# HCPL-3120_DIP_Gate_Driver_Circuit.net
KiCad netlist of a schematic drawn in Altium Designer
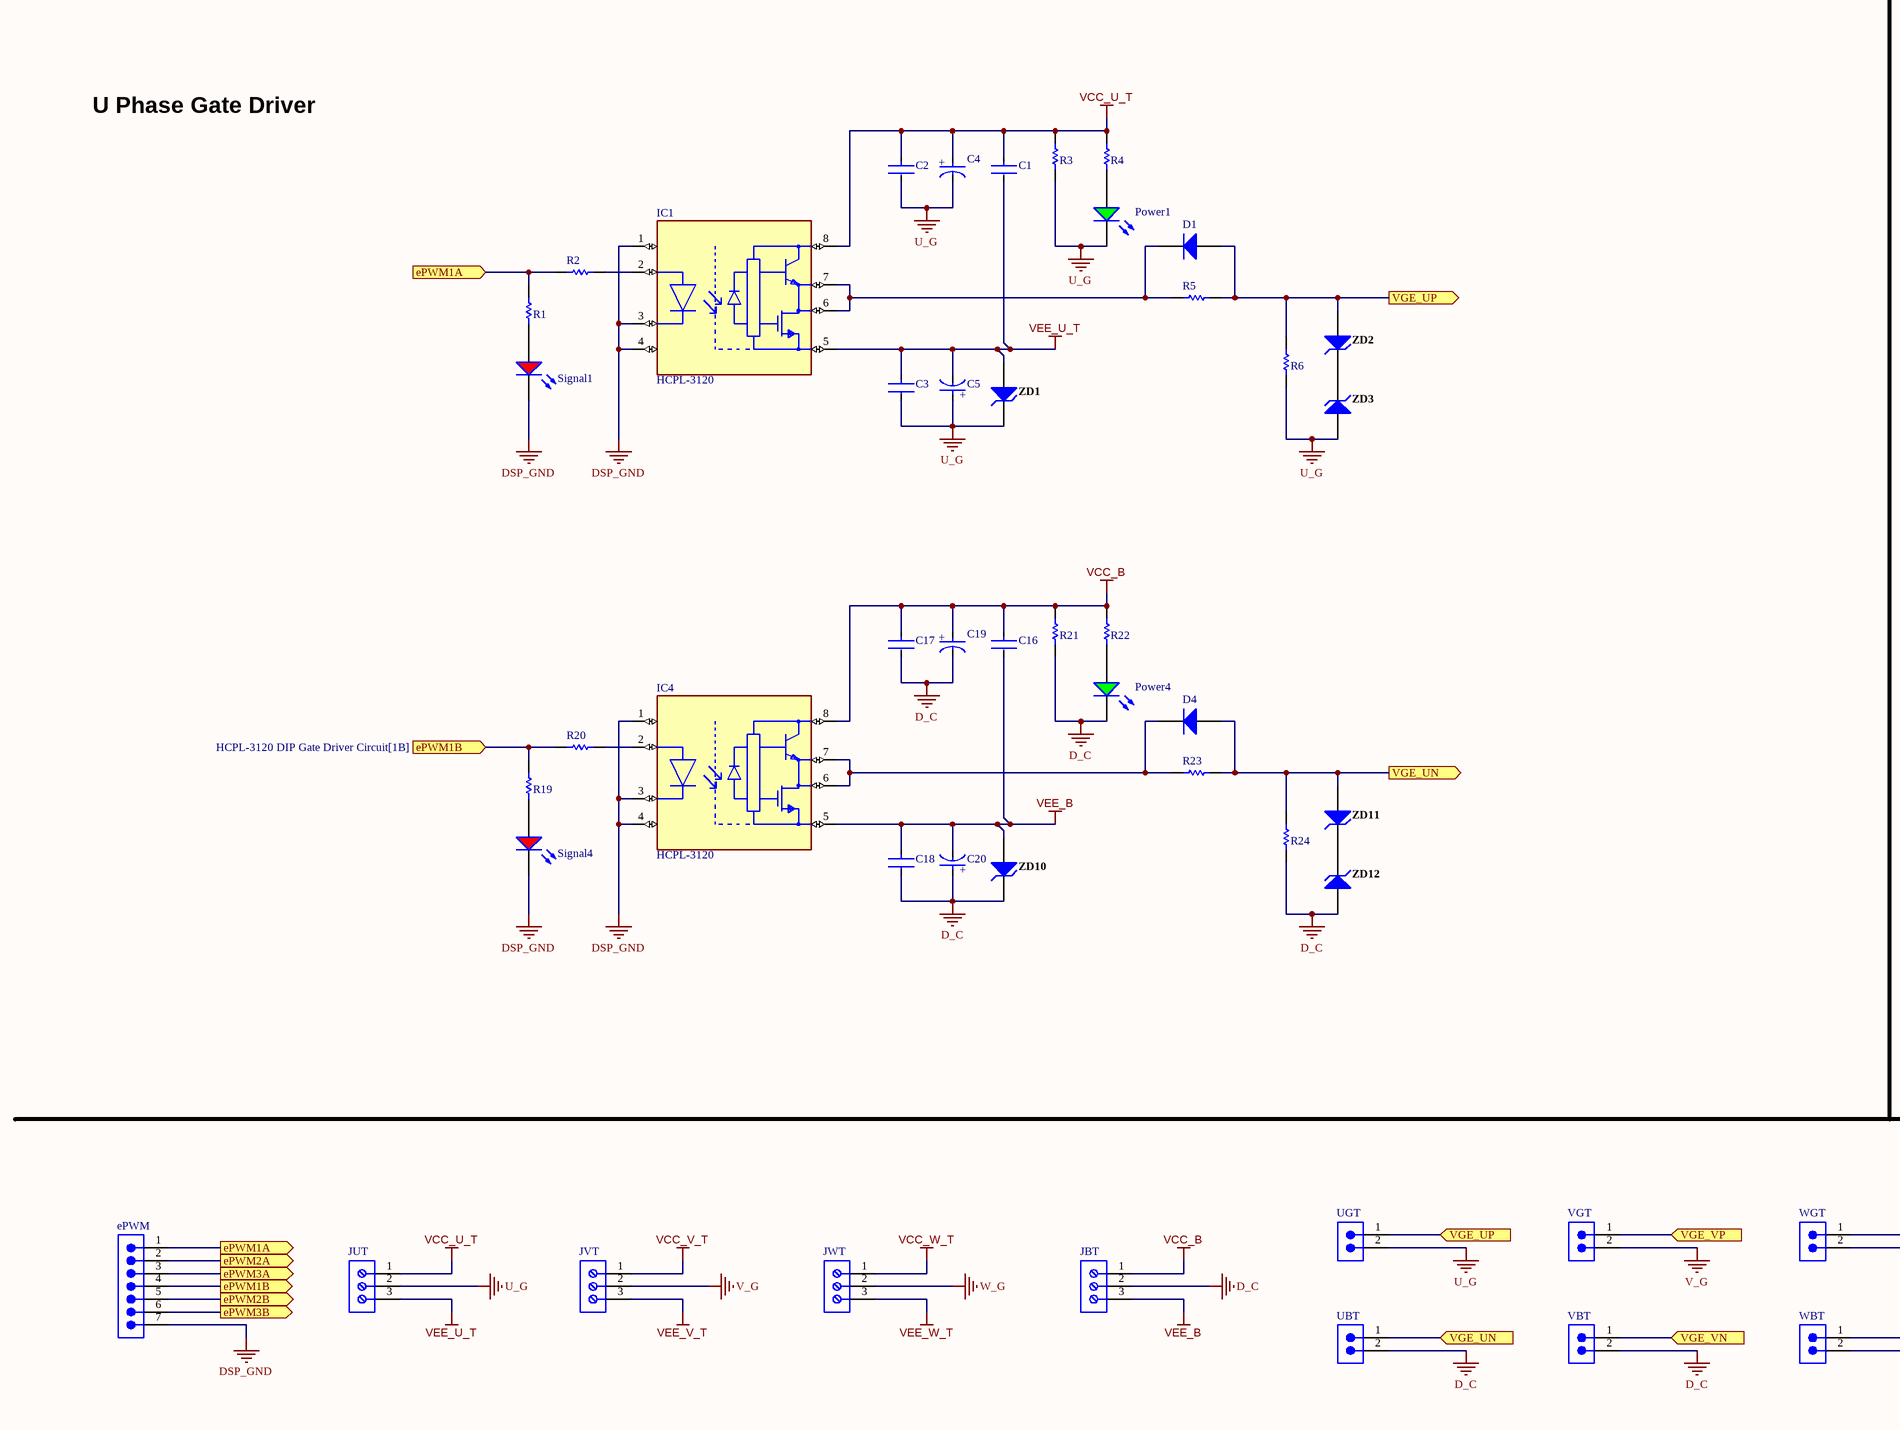
[diagram p0: HCPL-3120 DIP Gate Driver Circuit.SchDoc, left]
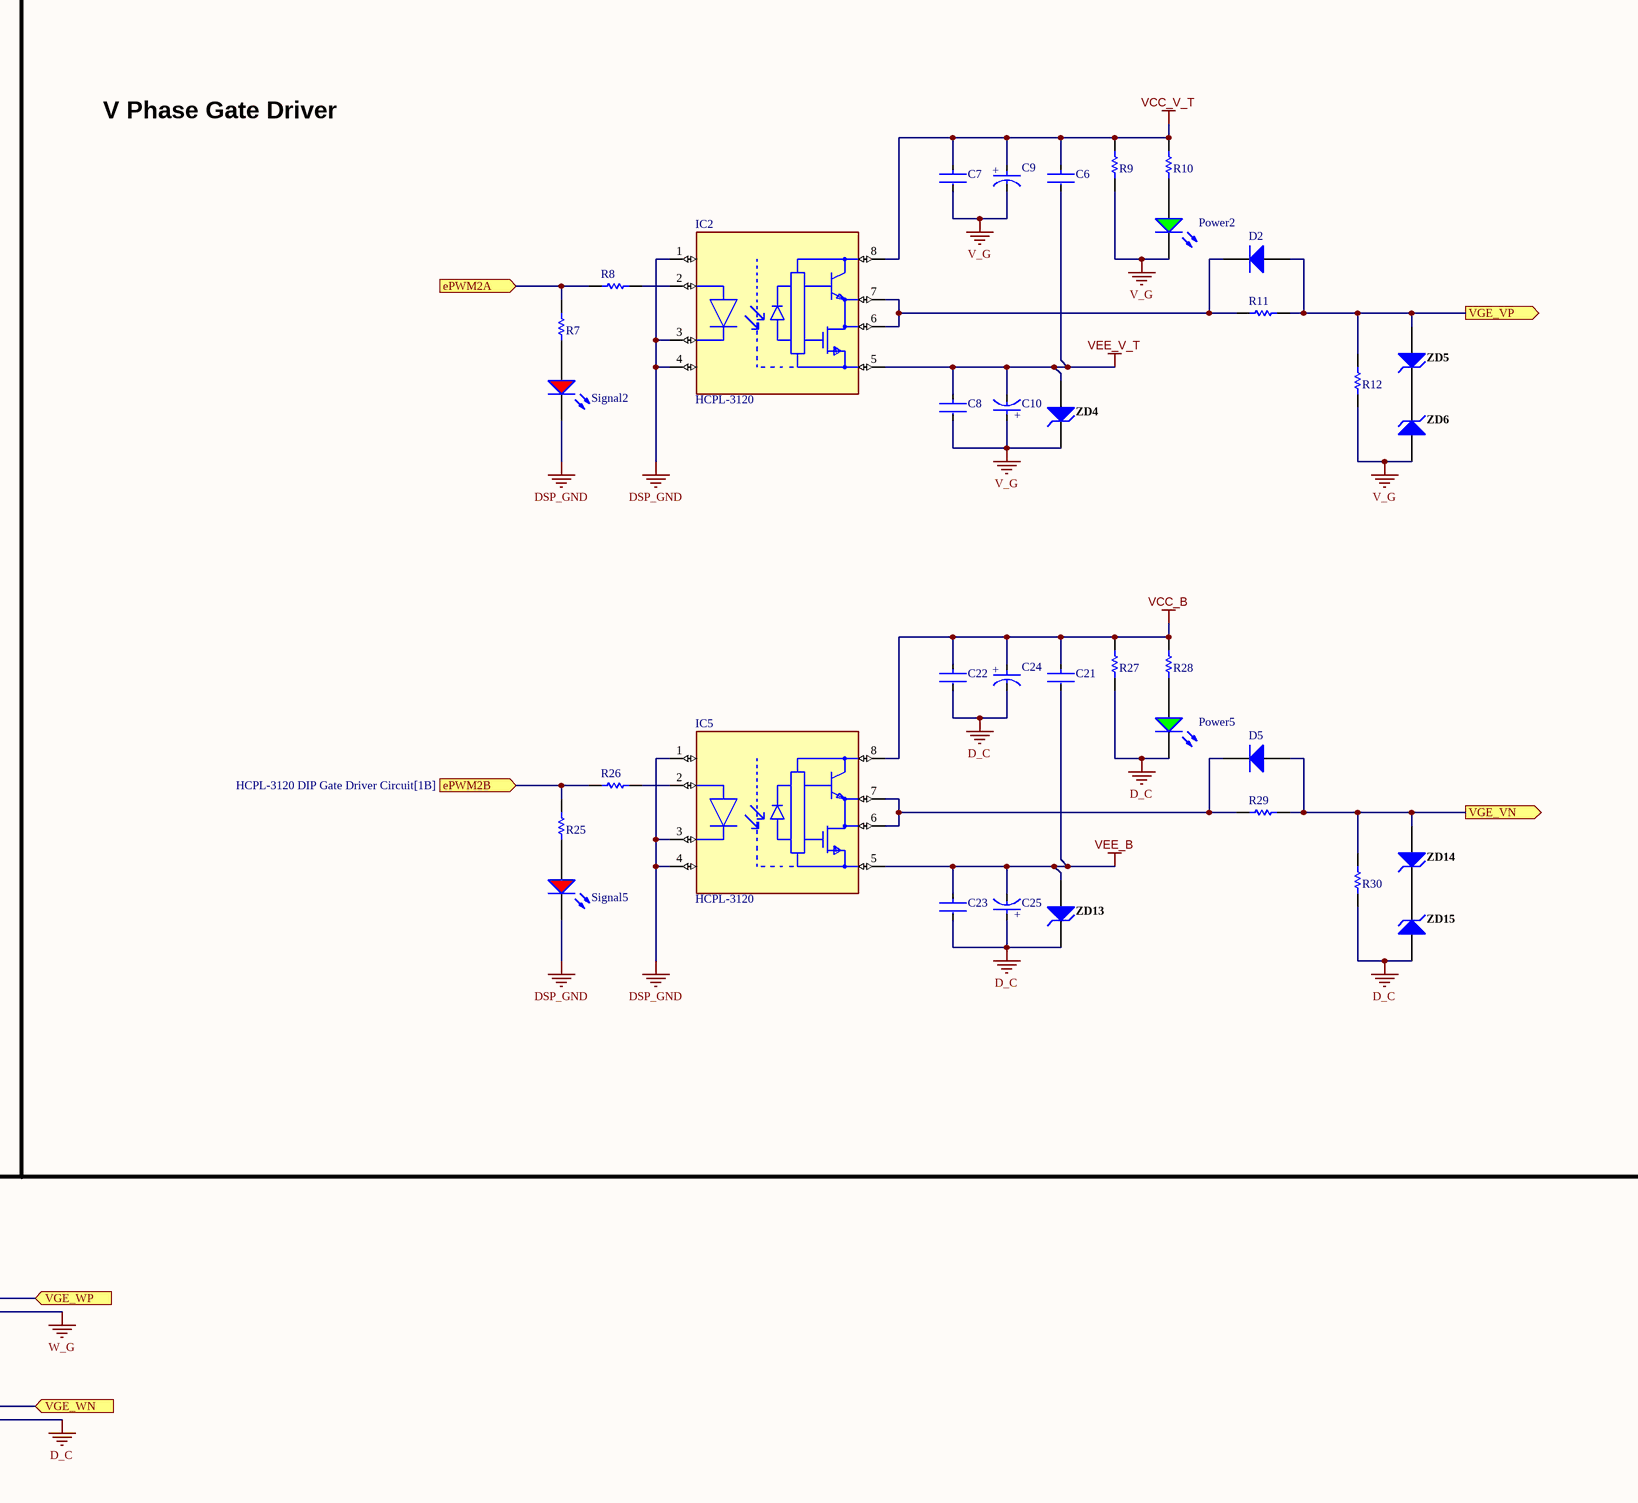
[diagram p1: HCPL-3120 DIP Gate Driver Circuit.SchDoc, middle]
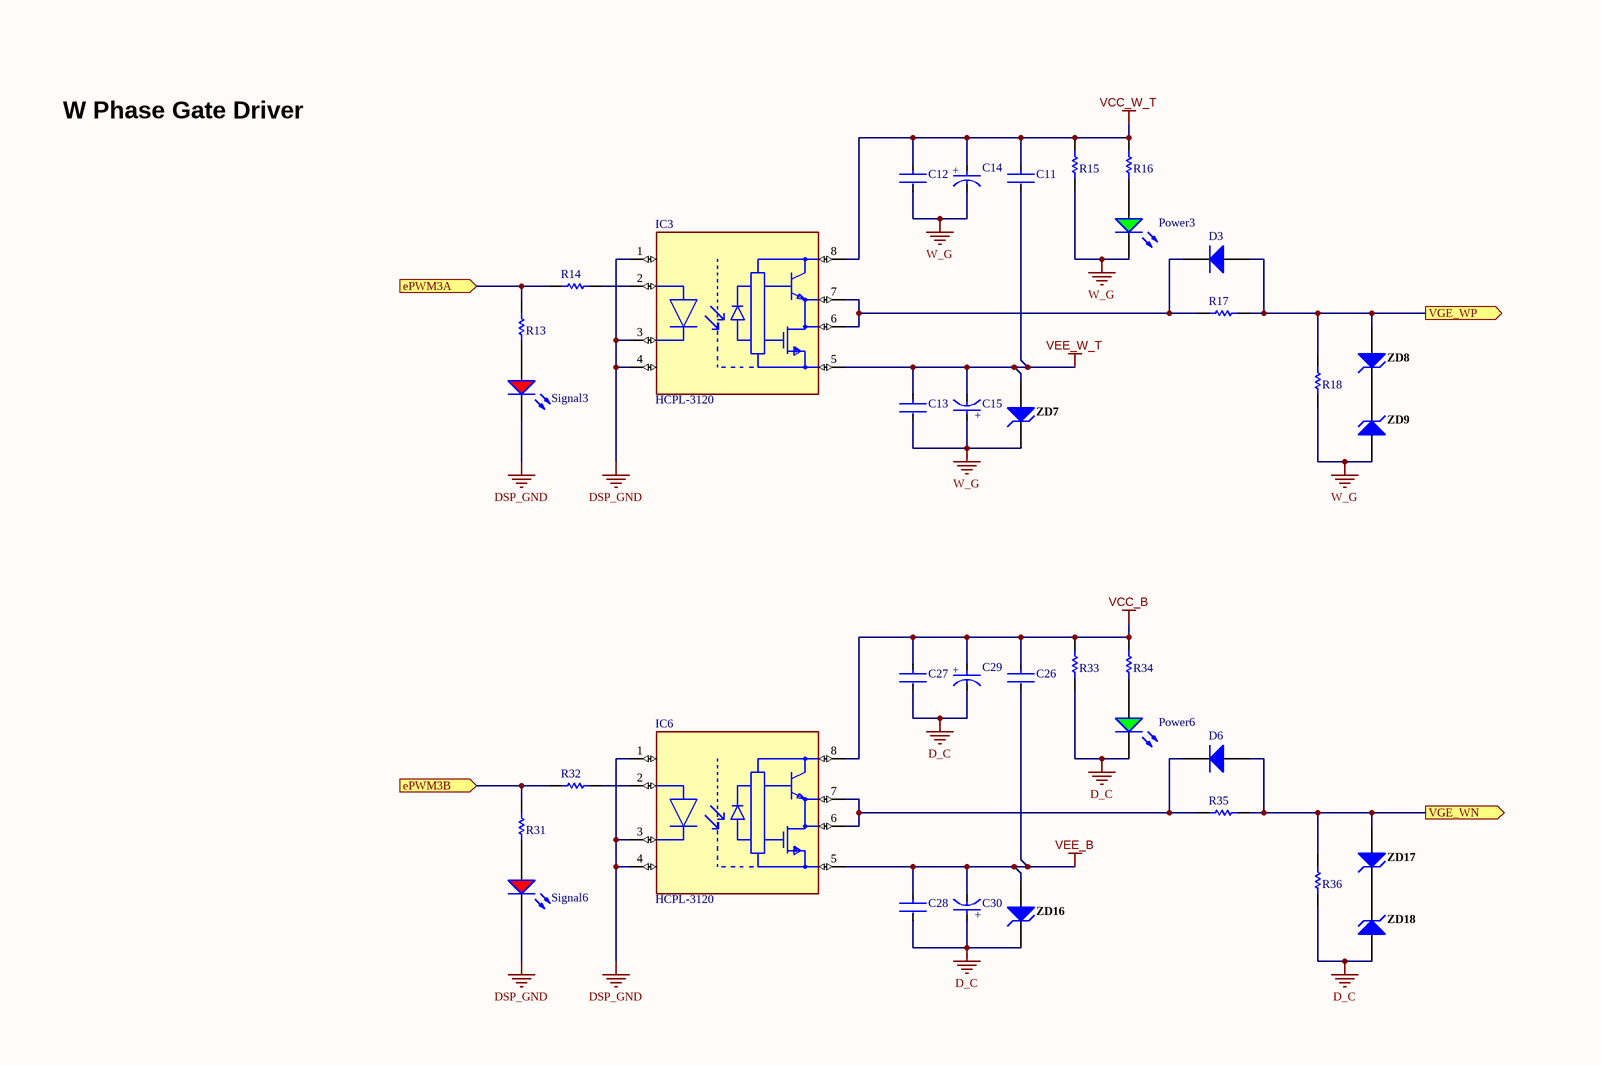
[diagram p2: HCPL-3120 DIP Gate Driver Circuit.SchDoc, right]

(export (version "E")
  (design (tool "Eeschema 10.0.6"))
  (components
    (comp (ref "C1")
      (value "SR205C104KAR")
      (footprint "FP-SR20-MFG")
      (description "CAP CER 0.1UF 50V X7R RADIAL")
      (fields (field (name "VOLTAGE") "50V") (field (name "TOLERANCE") "10%"))
      (libsource (lib "Altium Content Vault") (part "11868f565c42a9108669ba33697ecf6"))
    )
    (comp (ref "C2")
      (value "SR205C104KAR")
      (footprint "FP-SR20-MFG")
      (description "CAP CER 0.1UF 50V X7R RADIAL")
      (fields (field (name "VOLTAGE") "50V") (field (name "TOLERANCE") "10%"))
      (libsource (lib "Altium Content Vault") (part "11868f565c42a9108669ba33697ecf6"))
    )
    (comp (ref "C3")
      (value "SR205C104KAR")
      (footprint "FP-SR20-MFG")
      (description "CAP CER 0.1UF 50V X7R RADIAL")
      (fields (field (name "VOLTAGE") "50V") (field (name "TOLERANCE") "10%"))
      (libsource (lib "Altium Content Vault") (part "11868f565c42a9108669ba33697ecf6"))
    )
    (comp (ref "C4")
      (value "EEUTA1H101")
      (footprint "FP-RAD-TH-D_10_0_5-L_12_5-MFG")
      (description "Aluminum Electrolytic Capacitors (Radial Lead Type) AEC-Q200 Qualified 100uF ±20% 50V")
      (fields (field (name "TOLERANCE") "20%"))
      (libsource (lib "Altium Content Vault") (part "203bc49f2ac43e59fd269a8c329ed05"))
    )
    (comp (ref "C5")
      (value "EEUTA1H101")
      (footprint "FP-RAD-TH-D_10_0_5-L_12_5-MFG")
      (description "Aluminum Electrolytic Capacitors (Radial Lead Type) AEC-Q200 Qualified 100uF ±20% 50V")
      (fields (field (name "TOLERANCE") "20%"))
      (libsource (lib "Altium Content Vault") (part "203bc49f2ac43e59fd269a8c329ed05"))
    )
    (comp (ref "C6")
      (value "SR205C104KAR")
      (footprint "FP-SR20-MFG")
      (description "CAP CER 0.1UF 50V X7R RADIAL")
      (fields (field (name "VOLTAGE") "50V") (field (name "TOLERANCE") "10%"))
      (libsource (lib "Altium Content Vault") (part "11868f565c42a9108669ba33697ecf6"))
    )
    (comp (ref "C7")
      (value "SR205C104KAR")
      (footprint "FP-SR20-MFG")
      (description "CAP CER 0.1UF 50V X7R RADIAL")
      (fields (field (name "VOLTAGE") "50V") (field (name "TOLERANCE") "10%"))
      (libsource (lib "Altium Content Vault") (part "11868f565c42a9108669ba33697ecf6"))
    )
    (comp (ref "C8")
      (value "SR205C104KAR")
      (footprint "FP-SR20-MFG")
      (description "CAP CER 0.1UF 50V X7R RADIAL")
      (fields (field (name "VOLTAGE") "50V") (field (name "TOLERANCE") "10%"))
      (libsource (lib "Altium Content Vault") (part "11868f565c42a9108669ba33697ecf6"))
    )
    (comp (ref "C9")
      (value "EEUTA1H101")
      (footprint "FP-RAD-TH-D_10_0_5-L_12_5-MFG")
      (description "Aluminum Electrolytic Capacitors (Radial Lead Type) AEC-Q200 Qualified 100uF ±20% 50V")
      (fields (field (name "TOLERANCE") "20%"))
      (libsource (lib "Altium Content Vault") (part "203bc49f2ac43e59fd269a8c329ed05"))
    )
    (comp (ref "C10")
      (value "EEUTA1H101")
      (footprint "FP-RAD-TH-D_10_0_5-L_12_5-MFG")
      (description "Aluminum Electrolytic Capacitors (Radial Lead Type) AEC-Q200 Qualified 100uF ±20% 50V")
      (fields (field (name "TOLERANCE") "20%"))
      (libsource (lib "Altium Content Vault") (part "203bc49f2ac43e59fd269a8c329ed05"))
    )
    (comp (ref "C11")
      (value "SR205C104KAR")
      (footprint "FP-SR20-MFG")
      (description "CAP CER 0.1UF 50V X7R RADIAL")
      (fields (field (name "VOLTAGE") "50V") (field (name "TOLERANCE") "10%"))
      (libsource (lib "Altium Content Vault") (part "11868f565c42a9108669ba33697ecf6"))
    )
    (comp (ref "C12")
      (value "SR205C104KAR")
      (footprint "FP-SR20-MFG")
      (description "CAP CER 0.1UF 50V X7R RADIAL")
      (fields (field (name "VOLTAGE") "50V") (field (name "TOLERANCE") "10%"))
      (libsource (lib "Altium Content Vault") (part "11868f565c42a9108669ba33697ecf6"))
    )
    (comp (ref "C13")
      (value "SR205C104KAR")
      (footprint "FP-SR20-MFG")
      (description "CAP CER 0.1UF 50V X7R RADIAL")
      (fields (field (name "VOLTAGE") "50V") (field (name "TOLERANCE") "10%"))
      (libsource (lib "Altium Content Vault") (part "11868f565c42a9108669ba33697ecf6"))
    )
    (comp (ref "C14")
      (value "EEUTA1H101")
      (footprint "FP-RAD-TH-D_10_0_5-L_12_5-MFG")
      (description "Aluminum Electrolytic Capacitors (Radial Lead Type) AEC-Q200 Qualified 100uF ±20% 50V")
      (fields (field (name "TOLERANCE") "20%"))
      (libsource (lib "Altium Content Vault") (part "203bc49f2ac43e59fd269a8c329ed05"))
    )
    (comp (ref "C15")
      (value "EEUTA1H101")
      (footprint "FP-RAD-TH-D_10_0_5-L_12_5-MFG")
      (description "Aluminum Electrolytic Capacitors (Radial Lead Type) AEC-Q200 Qualified 100uF ±20% 50V")
      (fields (field (name "TOLERANCE") "20%"))
      (libsource (lib "Altium Content Vault") (part "203bc49f2ac43e59fd269a8c329ed05"))
    )
    (comp (ref "C16")
      (value "SR205C104KAR")
      (footprint "FP-SR20-MFG")
      (description "CAP CER 0.1UF 50V X7R RADIAL")
      (fields (field (name "VOLTAGE") "50V") (field (name "TOLERANCE") "10%"))
      (libsource (lib "Altium Content Vault") (part "11868f565c42a9108669ba33697ecf6"))
    )
    (comp (ref "C17")
      (value "SR205C104KAR")
      (footprint "FP-SR20-MFG")
      (description "CAP CER 0.1UF 50V X7R RADIAL")
      (fields (field (name "VOLTAGE") "50V") (field (name "TOLERANCE") "10%"))
      (libsource (lib "Altium Content Vault") (part "11868f565c42a9108669ba33697ecf6"))
    )
    (comp (ref "C18")
      (value "SR205C104KAR")
      (footprint "FP-SR20-MFG")
      (description "CAP CER 0.1UF 50V X7R RADIAL")
      (fields (field (name "VOLTAGE") "50V") (field (name "TOLERANCE") "10%"))
      (libsource (lib "Altium Content Vault") (part "11868f565c42a9108669ba33697ecf6"))
    )
    (comp (ref "C19")
      (value "EEUTA1H101")
      (footprint "FP-RAD-TH-D_10_0_5-L_12_5-MFG")
      (description "Aluminum Electrolytic Capacitors (Radial Lead Type) AEC-Q200 Qualified 100uF ±20% 50V")
      (fields (field (name "TOLERANCE") "20%"))
      (libsource (lib "Altium Content Vault") (part "203bc49f2ac43e59fd269a8c329ed05"))
    )
    (comp (ref "C20")
      (value "EEUTA1H101")
      (footprint "FP-RAD-TH-D_10_0_5-L_12_5-MFG")
      (description "Aluminum Electrolytic Capacitors (Radial Lead Type) AEC-Q200 Qualified 100uF ±20% 50V")
      (fields (field (name "TOLERANCE") "20%"))
      (libsource (lib "Altium Content Vault") (part "203bc49f2ac43e59fd269a8c329ed05"))
    )
    (comp (ref "C21")
      (value "SR205C104KAR")
      (footprint "FP-SR20-MFG")
      (description "CAP CER 0.1UF 50V X7R RADIAL")
      (fields (field (name "VOLTAGE") "50V") (field (name "TOLERANCE") "10%"))
      (libsource (lib "Altium Content Vault") (part "11868f565c42a9108669ba33697ecf6"))
    )
    (comp (ref "C22")
      (value "SR205C104KAR")
      (footprint "FP-SR20-MFG")
      (description "CAP CER 0.1UF 50V X7R RADIAL")
      (fields (field (name "VOLTAGE") "50V") (field (name "TOLERANCE") "10%"))
      (libsource (lib "Altium Content Vault") (part "11868f565c42a9108669ba33697ecf6"))
    )
    (comp (ref "C23")
      (value "SR205C104KAR")
      (footprint "FP-SR20-MFG")
      (description "CAP CER 0.1UF 50V X7R RADIAL")
      (fields (field (name "VOLTAGE") "50V") (field (name "TOLERANCE") "10%"))
      (libsource (lib "Altium Content Vault") (part "11868f565c42a9108669ba33697ecf6"))
    )
    (comp (ref "C24")
      (value "EEUTA1H101")
      (footprint "FP-RAD-TH-D_10_0_5-L_12_5-MFG")
      (description "Aluminum Electrolytic Capacitors (Radial Lead Type) AEC-Q200 Qualified 100uF ±20% 50V")
      (fields (field (name "TOLERANCE") "20%"))
      (libsource (lib "Altium Content Vault") (part "203bc49f2ac43e59fd269a8c329ed05"))
    )
    (comp (ref "C25")
      (value "EEUTA1H101")
      (footprint "FP-RAD-TH-D_10_0_5-L_12_5-MFG")
      (description "Aluminum Electrolytic Capacitors (Radial Lead Type) AEC-Q200 Qualified 100uF ±20% 50V")
      (fields (field (name "TOLERANCE") "20%"))
      (libsource (lib "Altium Content Vault") (part "203bc49f2ac43e59fd269a8c329ed05"))
    )
    (comp (ref "C26")
      (value "SR205C104KAR")
      (footprint "FP-SR20-MFG")
      (description "CAP CER 0.1UF 50V X7R RADIAL")
      (fields (field (name "VOLTAGE") "50V") (field (name "TOLERANCE") "10%"))
      (libsource (lib "Altium Content Vault") (part "11868f565c42a9108669ba33697ecf6"))
    )
    (comp (ref "C27")
      (value "SR205C104KAR")
      (footprint "FP-SR20-MFG")
      (description "CAP CER 0.1UF 50V X7R RADIAL")
      (fields (field (name "VOLTAGE") "50V") (field (name "TOLERANCE") "10%"))
      (libsource (lib "Altium Content Vault") (part "11868f565c42a9108669ba33697ecf6"))
    )
    (comp (ref "C28")
      (value "SR205C104KAR")
      (footprint "FP-SR20-MFG")
      (description "CAP CER 0.1UF 50V X7R RADIAL")
      (fields (field (name "VOLTAGE") "50V") (field (name "TOLERANCE") "10%"))
      (libsource (lib "Altium Content Vault") (part "11868f565c42a9108669ba33697ecf6"))
    )
    (comp (ref "C29")
      (value "EEUTA1H101")
      (footprint "FP-RAD-TH-D_10_0_5-L_12_5-MFG")
      (description "Aluminum Electrolytic Capacitors (Radial Lead Type) AEC-Q200 Qualified 100uF ±20% 50V")
      (fields (field (name "TOLERANCE") "20%"))
      (libsource (lib "Altium Content Vault") (part "203bc49f2ac43e59fd269a8c329ed05"))
    )
    (comp (ref "C30")
      (value "EEUTA1H101")
      (footprint "FP-RAD-TH-D_10_0_5-L_12_5-MFG")
      (description "Aluminum Electrolytic Capacitors (Radial Lead Type) AEC-Q200 Qualified 100uF ±20% 50V")
      (fields (field (name "TOLERANCE") "20%"))
      (libsource (lib "Altium Content Vault") (part "203bc49f2ac43e59fd269a8c329ed05"))
    )
    (comp (ref "D1")
      (value "1N4007-B")
      (footprint "DIOD-DO-41-P-2_V")
      (description "30V, 1A Rectifier, 8 pF, -65 to 150 degC, 2-Pin DO-41 Plastic, RoHS, Bulk")
      (fields (field (name "MANUFACTURER") "Diodes Inc"))
      (libsource (lib "Altium Content Vault") (part "DIOD-D-A1K2-2"))
    )
    (comp (ref "D2")
      (value "1N4007-B")
      (footprint "DIOD-DO-41-P-2_V")
      (description "30V, 1A Rectifier, 8 pF, -65 to 150 degC, 2-Pin DO-41 Plastic, RoHS, Bulk")
      (fields (field (name "MANUFACTURER") "Diodes Inc"))
      (libsource (lib "Altium Content Vault") (part "DIOD-D-A1K2-2"))
    )
    (comp (ref "D3")
      (value "1N4007-B")
      (footprint "DIOD-DO-41-P-2_V")
      (description "30V, 1A Rectifier, 8 pF, -65 to 150 degC, 2-Pin DO-41 Plastic, RoHS, Bulk")
      (fields (field (name "MANUFACTURER") "Diodes Inc"))
      (libsource (lib "Altium Content Vault") (part "DIOD-D-A1K2-2"))
    )
    (comp (ref "D4")
      (value "1N4007-B")
      (footprint "DIOD-DO-41-P-2_V")
      (description "30V, 1A Rectifier, 8 pF, -65 to 150 degC, 2-Pin DO-41 Plastic, RoHS, Bulk")
      (fields (field (name "MANUFACTURER") "Diodes Inc"))
      (libsource (lib "Altium Content Vault") (part "DIOD-D-A1K2-2"))
    )
    (comp (ref "D5")
      (value "1N4007-B")
      (footprint "DIOD-DO-41-P-2_V")
      (description "30V, 1A Rectifier, 8 pF, -65 to 150 degC, 2-Pin DO-41 Plastic, RoHS, Bulk")
      (fields (field (name "MANUFACTURER") "Diodes Inc"))
      (libsource (lib "Altium Content Vault") (part "DIOD-D-A1K2-2"))
    )
    (comp (ref "D6")
      (value "1N4007-B")
      (footprint "DIOD-DO-41-P-2_V")
      (description "30V, 1A Rectifier, 8 pF, -65 to 150 degC, 2-Pin DO-41 Plastic, RoHS, Bulk")
      (fields (field (name "MANUFACTURER") "Diodes Inc"))
      (libsource (lib "Altium Content Vault") (part "DIOD-D-A1K2-2"))
    )
    (comp (ref "ePWM")
      (value "61300711121")
      (footprint "61300711121")
      (libsource (lib "Altium Content Vault") (part "Header_Male_1R_07P"))
    )
    (comp (ref "IC1")
      (value "HCPL-3120")
      (footprint "PCBComponent_1")
      (description "OPTOISO 3.75KV 1CH GATE DVR 8DIP")
      (libsource (lib "HCPL-3120") (part "CMP-18400-000012-1"))
    )
    (comp (ref "IC2")
      (value "HCPL-3120")
      (footprint "PCBComponent_1")
      (description "OPTOISO 3.75KV 1CH GATE DVR 8DIP")
      (libsource (lib "HCPL-3120") (part "CMP-18400-000012-1"))
    )
    (comp (ref "IC3")
      (value "HCPL-3120")
      (footprint "PCBComponent_1")
      (description "OPTOISO 3.75KV 1CH GATE DVR 8DIP")
      (libsource (lib "HCPL-3120") (part "CMP-18400-000012-1"))
    )
    (comp (ref "IC4")
      (value "HCPL-3120")
      (footprint "PCBComponent_1")
      (description "OPTOISO 3.75KV 1CH GATE DVR 8DIP")
      (libsource (lib "HCPL-3120") (part "CMP-18400-000012-1"))
    )
    (comp (ref "IC5")
      (value "HCPL-3120")
      (footprint "PCBComponent_1")
      (description "OPTOISO 3.75KV 1CH GATE DVR 8DIP")
      (libsource (lib "HCPL-3120") (part "CMP-18400-000012-1"))
    )
    (comp (ref "IC6")
      (value "HCPL-3120")
      (footprint "PCBComponent_1")
      (description "OPTOISO 3.75KV 1CH GATE DVR 8DIP")
      (libsource (lib "HCPL-3120") (part "CMP-18400-000012-1"))
    )
    (comp (ref "JBT")
      (value "691214110003")
      (footprint "691214110003")
      (fields (field (name "VOLTAGE") "300V"))
      (libsource (lib "Altium Content Vault") (part "TBL - 1R - 03P - Screw"))
    )
    (comp (ref "JUT")
      (value "691214110003")
      (footprint "691214110003")
      (fields (field (name "VOLTAGE") "300V"))
      (libsource (lib "Altium Content Vault") (part "TBL - 1R - 03P - Screw"))
    )
    (comp (ref "JVT")
      (value "691214110003")
      (footprint "691214110003")
      (fields (field (name "VOLTAGE") "300V"))
      (libsource (lib "Altium Content Vault") (part "TBL - 1R - 03P - Screw"))
    )
    (comp (ref "JWT")
      (value "691214110003")
      (footprint "691214110003")
      (fields (field (name "VOLTAGE") "300V"))
      (libsource (lib "Altium Content Vault") (part "TBL - 1R - 03P - Screw"))
    )
    (comp (ref "Power1")
      (value "151031VS04000")
      (footprint "WL-TMRC_D3.95H5.3")
      (description "Led, Green, T-1 (3Mm), 570 Nm, 2.1 V, 30 Ma, 120 Mcd")
      (libsource (lib "Altium Content Vault") (part "LED_Green_1A-2K"))
    )
    (comp (ref "Power2")
      (value "151031VS04000")
      (footprint "WL-TMRC_D3.95H5.3")
      (description "Led, Green, T-1 (3Mm), 570 Nm, 2.1 V, 30 Ma, 120 Mcd")
      (libsource (lib "Altium Content Vault") (part "LED_Green_1A-2K"))
    )
    (comp (ref "Power3")
      (value "151031VS04000")
      (footprint "WL-TMRC_D3.95H5.3")
      (description "Led, Green, T-1 (3Mm), 570 Nm, 2.1 V, 30 Ma, 120 Mcd")
      (libsource (lib "Altium Content Vault") (part "LED_Green_1A-2K"))
    )
    (comp (ref "Power4")
      (value "151031VS04000")
      (footprint "WL-TMRC_D3.95H5.3")
      (description "Led, Green, T-1 (3Mm), 570 Nm, 2.1 V, 30 Ma, 120 Mcd")
      (libsource (lib "Altium Content Vault") (part "LED_Green_1A-2K"))
    )
    (comp (ref "Power5")
      (value "151031VS04000")
      (footprint "WL-TMRC_D3.95H5.3")
      (description "Led, Green, T-1 (3Mm), 570 Nm, 2.1 V, 30 Ma, 120 Mcd")
      (libsource (lib "Altium Content Vault") (part "LED_Green_1A-2K"))
    )
    (comp (ref "Power6")
      (value "151031VS04000")
      (footprint "WL-TMRC_D3.95H5.3")
      (description "Led, Green, T-1 (3Mm), 570 Nm, 2.1 V, 30 Ma, 120 Mcd")
      (libsource (lib "Altium Content Vault") (part "LED_Green_1A-2K"))
    )
    (comp (ref "R1")
      (value "MFR-25FBF52-1K")
      (footprint "RESA60-630X240")
      (description "Axial Resistor, 1K Ohm, +/- 1%, 0.25W, -55 to 155 degC, 2-Pin THD, RoHS, Bulk")
      (fields (field (name "TOLERANCE") "1%"))
      (libsource (lib "Altium Content Vault") (part "RES-2"))
    )
    (comp (ref "R2")
      (value "MFR-25FBF52-221R")
      (footprint "RESA60-630X240")
      (description "Axial Resistor, 330 Ohm, +/- 1%, 0.25W, -55 to 155 degC, 2-Pin THD, RoHS, Bulk")
      (libsource (lib "Altium Content Vault") (part "RES-2"))
    )
    (comp (ref "R3")
      (value "MFR-25FBF52-1K")
      (footprint "RESA60-630X240")
      (description "Axial Resistor, 1K Ohm, +/- 1%, 0.25W, -55 to 155 degC, 2-Pin THD, RoHS, Bulk")
      (fields (field (name "TOLERANCE") "1%"))
      (libsource (lib "Altium Content Vault") (part "RES-2"))
    )
    (comp (ref "R4")
      (value "MFR-25FBF52-1K")
      (footprint "RESA60-630X240")
      (description "Axial Resistor, 1K Ohm, +/- 1%, 0.25W, -55 to 155 degC, 2-Pin THD, RoHS, Bulk")
      (fields (field (name "TOLERANCE") "1%"))
      (libsource (lib "Altium Content Vault") (part "RES-2"))
    )
    (comp (ref "R5")
      (value "MFR-25FBF52-47R5")
      (footprint "RESA60-630X240")
      (description "Axial Resistor, 30 Ohm, +/- 1%, 0.25 W, -55 to 155 degC, 2-Pin THD, RoHS, Bulk")
      (libsource (lib "Altium Content Vault") (part "RES-2"))
    )
    (comp (ref "R6")
      (value "MFR-25FBF5210K")
      (footprint "RESA60-630X240")
      (description "Axial Resistor, 10K Ohm, +/- 1%, 0.25 W, -55 to 155 degC, 2-Pin THD, RoHS, Bulk")
      (fields (field (name "TOLERANCE") "1%") (field (name "MANUFACTURER") "Yageo"))
      (libsource (lib "Altium Content Vault") (part "RES-2"))
    )
    (comp (ref "R7")
      (value "MFR-25FBF52-1K")
      (footprint "RESA60-630X240")
      (description "Axial Resistor, 1K Ohm, +/- 1%, 0.25W, -55 to 155 degC, 2-Pin THD, RoHS, Bulk")
      (fields (field (name "TOLERANCE") "1%"))
      (libsource (lib "Altium Content Vault") (part "RES-2"))
    )
    (comp (ref "R8")
      (value "MFR-25FBF52-221R")
      (footprint "RESA60-630X240")
      (description "Axial Resistor, 330 Ohm, +/- 1%, 0.25W, -55 to 155 degC, 2-Pin THD, RoHS, Bulk")
      (libsource (lib "Altium Content Vault") (part "RES-2"))
    )
    (comp (ref "R9")
      (value "MFR-25FBF52-1K")
      (footprint "RESA60-630X240")
      (description "Axial Resistor, 1K Ohm, +/- 1%, 0.25W, -55 to 155 degC, 2-Pin THD, RoHS, Bulk")
      (fields (field (name "TOLERANCE") "1%"))
      (libsource (lib "Altium Content Vault") (part "RES-2"))
    )
    (comp (ref "R10")
      (value "MFR-25FBF52-1K")
      (footprint "RESA60-630X240")
      (description "Axial Resistor, 1K Ohm, +/- 1%, 0.25W, -55 to 155 degC, 2-Pin THD, RoHS, Bulk")
      (fields (field (name "TOLERANCE") "1%"))
      (libsource (lib "Altium Content Vault") (part "RES-2"))
    )
    (comp (ref "R11")
      (value "MFR-25FBF52-47R5")
      (footprint "RESA60-630X240")
      (description "Axial Resistor, 30 Ohm, +/- 1%, 0.25 W, -55 to 155 degC, 2-Pin THD, RoHS, Bulk")
      (libsource (lib "Altium Content Vault") (part "RES-2"))
    )
    (comp (ref "R12")
      (value "MFR-25FBF5210K")
      (footprint "RESA60-630X240")
      (description "Axial Resistor, 10K Ohm, +/- 1%, 0.25 W, -55 to 155 degC, 2-Pin THD, RoHS, Bulk")
      (fields (field (name "TOLERANCE") "1%") (field (name "MANUFACTURER") "Yageo"))
      (libsource (lib "Altium Content Vault") (part "RES-2"))
    )
    (comp (ref "R13")
      (value "MFR-25FBF52-1K")
      (footprint "RESA60-630X240")
      (description "Axial Resistor, 1K Ohm, +/- 1%, 0.25W, -55 to 155 degC, 2-Pin THD, RoHS, Bulk")
      (fields (field (name "TOLERANCE") "1%"))
      (libsource (lib "Altium Content Vault") (part "RES-2"))
    )
    (comp (ref "R14")
      (value "MFR-25FBF52-221R")
      (footprint "RESA60-630X240")
      (description "Axial Resistor, 330 Ohm, +/- 1%, 0.25W, -55 to 155 degC, 2-Pin THD, RoHS, Bulk")
      (libsource (lib "Altium Content Vault") (part "RES-2"))
    )
    (comp (ref "R15")
      (value "MFR-25FBF52-1K")
      (footprint "RESA60-630X240")
      (description "Axial Resistor, 1K Ohm, +/- 1%, 0.25W, -55 to 155 degC, 2-Pin THD, RoHS, Bulk")
      (fields (field (name "TOLERANCE") "1%"))
      (libsource (lib "Altium Content Vault") (part "RES-2"))
    )
    (comp (ref "R16")
      (value "MFR-25FBF52-1K")
      (footprint "RESA60-630X240")
      (description "Axial Resistor, 1K Ohm, +/- 1%, 0.25W, -55 to 155 degC, 2-Pin THD, RoHS, Bulk")
      (fields (field (name "TOLERANCE") "1%"))
      (libsource (lib "Altium Content Vault") (part "RES-2"))
    )
    (comp (ref "R17")
      (value "MFR-25FBF52-47R5")
      (footprint "RESA60-630X240")
      (description "Axial Resistor, 30 Ohm, +/- 1%, 0.25 W, -55 to 155 degC, 2-Pin THD, RoHS, Bulk")
      (libsource (lib "Altium Content Vault") (part "RES-2"))
    )
    (comp (ref "R18")
      (value "MFR-25FBF5210K")
      (footprint "RESA60-630X240")
      (description "Axial Resistor, 10K Ohm, +/- 1%, 0.25 W, -55 to 155 degC, 2-Pin THD, RoHS, Bulk")
      (fields (field (name "TOLERANCE") "1%") (field (name "MANUFACTURER") "Yageo"))
      (libsource (lib "Altium Content Vault") (part "RES-2"))
    )
    (comp (ref "R19")
      (value "MFR-25FBF52-1K")
      (footprint "RESA60-630X240")
      (description "Axial Resistor, 1K Ohm, +/- 1%, 0.25W, -55 to 155 degC, 2-Pin THD, RoHS, Bulk")
      (fields (field (name "TOLERANCE") "1%"))
      (libsource (lib "Altium Content Vault") (part "RES-2"))
    )
    (comp (ref "R20")
      (value "MFR-25FBF52-221R")
      (footprint "RESA60-630X240")
      (description "Axial Resistor, 330 Ohm, +/- 1%, 0.25W, -55 to 155 degC, 2-Pin THD, RoHS, Bulk")
      (libsource (lib "Altium Content Vault") (part "RES-2"))
    )
    (comp (ref "R21")
      (value "MFR-25FBF52-1K")
      (footprint "RESA60-630X240")
      (description "Axial Resistor, 1K Ohm, +/- 1%, 0.25W, -55 to 155 degC, 2-Pin THD, RoHS, Bulk")
      (fields (field (name "TOLERANCE") "1%"))
      (libsource (lib "Altium Content Vault") (part "RES-2"))
    )
    (comp (ref "R22")
      (value "MFR-25FBF52-1K")
      (footprint "RESA60-630X240")
      (description "Axial Resistor, 1K Ohm, +/- 1%, 0.25W, -55 to 155 degC, 2-Pin THD, RoHS, Bulk")
      (fields (field (name "TOLERANCE") "1%"))
      (libsource (lib "Altium Content Vault") (part "RES-2"))
    )
    (comp (ref "R23")
      (value "MFR-25FBF52-47R5")
      (footprint "RESA60-630X240")
      (description "Axial Resistor, 30 Ohm, +/- 1%, 0.25 W, -55 to 155 degC, 2-Pin THD, RoHS, Bulk")
      (libsource (lib "Altium Content Vault") (part "RES-2"))
    )
    (comp (ref "R24")
      (value "MFR-25FBF5210K")
      (footprint "RESA60-630X240")
      (description "Axial Resistor, 10K Ohm, +/- 1%, 0.25 W, -55 to 155 degC, 2-Pin THD, RoHS, Bulk")
      (fields (field (name "TOLERANCE") "1%") (field (name "MANUFACTURER") "Yageo"))
      (libsource (lib "Altium Content Vault") (part "RES-2"))
    )
    (comp (ref "R25")
      (value "MFR-25FBF52-1K")
      (footprint "RESA60-630X240")
      (description "Axial Resistor, 1K Ohm, +/- 1%, 0.25W, -55 to 155 degC, 2-Pin THD, RoHS, Bulk")
      (fields (field (name "TOLERANCE") "1%"))
      (libsource (lib "Altium Content Vault") (part "RES-2"))
    )
    (comp (ref "R26")
      (value "MFR-25FBF52-221R")
      (footprint "RESA60-630X240")
      (description "Axial Resistor, 330 Ohm, +/- 1%, 0.25W, -55 to 155 degC, 2-Pin THD, RoHS, Bulk")
      (libsource (lib "Altium Content Vault") (part "RES-2"))
    )
    (comp (ref "R27")
      (value "MFR-25FBF52-1K")
      (footprint "RESA60-630X240")
      (description "Axial Resistor, 1K Ohm, +/- 1%, 0.25W, -55 to 155 degC, 2-Pin THD, RoHS, Bulk")
      (fields (field (name "TOLERANCE") "1%"))
      (libsource (lib "Altium Content Vault") (part "RES-2"))
    )
    (comp (ref "R28")
      (value "MFR-25FBF52-1K")
      (footprint "RESA60-630X240")
      (description "Axial Resistor, 1K Ohm, +/- 1%, 0.25W, -55 to 155 degC, 2-Pin THD, RoHS, Bulk")
      (fields (field (name "TOLERANCE") "1%"))
      (libsource (lib "Altium Content Vault") (part "RES-2"))
    )
    (comp (ref "R29")
      (value "MFR-25FBF52-47R5")
      (footprint "RESA60-630X240")
      (description "Axial Resistor, 30 Ohm, +/- 1%, 0.25 W, -55 to 155 degC, 2-Pin THD, RoHS, Bulk")
      (libsource (lib "Altium Content Vault") (part "RES-2"))
    )
    (comp (ref "R30")
      (value "MFR-25FBF5210K")
      (footprint "RESA60-630X240")
      (description "Axial Resistor, 10K Ohm, +/- 1%, 0.25 W, -55 to 155 degC, 2-Pin THD, RoHS, Bulk")
      (fields (field (name "TOLERANCE") "1%") (field (name "MANUFACTURER") "Yageo"))
      (libsource (lib "Altium Content Vault") (part "RES-2"))
    )
    (comp (ref "R31")
      (value "MFR-25FBF52-1K")
      (footprint "RESA60-630X240")
      (description "Axial Resistor, 1K Ohm, +/- 1%, 0.25W, -55 to 155 degC, 2-Pin THD, RoHS, Bulk")
      (fields (field (name "TOLERANCE") "1%"))
      (libsource (lib "Altium Content Vault") (part "RES-2"))
    )
    (comp (ref "R32")
      (value "MFR-25FBF52-221R")
      (footprint "RESA60-630X240")
      (description "Axial Resistor, 330 Ohm, +/- 1%, 0.25W, -55 to 155 degC, 2-Pin THD, RoHS, Bulk")
      (libsource (lib "Altium Content Vault") (part "RES-2"))
    )
    (comp (ref "R33")
      (value "MFR-25FBF52-1K")
      (footprint "RESA60-630X240")
      (description "Axial Resistor, 1K Ohm, +/- 1%, 0.25W, -55 to 155 degC, 2-Pin THD, RoHS, Bulk")
      (fields (field (name "TOLERANCE") "1%"))
      (libsource (lib "Altium Content Vault") (part "RES-2"))
    )
    (comp (ref "R34")
      (value "MFR-25FBF52-1K")
      (footprint "RESA60-630X240")
      (description "Axial Resistor, 1K Ohm, +/- 1%, 0.25W, -55 to 155 degC, 2-Pin THD, RoHS, Bulk")
      (fields (field (name "TOLERANCE") "1%"))
      (libsource (lib "Altium Content Vault") (part "RES-2"))
    )
    (comp (ref "R35")
      (value "MFR-25FBF52-47R5")
      (footprint "RESA60-630X240")
      (description "Axial Resistor, 30 Ohm, +/- 1%, 0.25 W, -55 to 155 degC, 2-Pin THD, RoHS, Bulk")
      (libsource (lib "Altium Content Vault") (part "RES-2"))
    )
    (comp (ref "R36")
      (value "MFR-25FBF5210K")
      (footprint "RESA60-630X240")
      (description "Axial Resistor, 10K Ohm, +/- 1%, 0.25 W, -55 to 155 degC, 2-Pin THD, RoHS, Bulk")
      (fields (field (name "TOLERANCE") "1%") (field (name "MANUFACTURER") "Yageo"))
      (libsource (lib "Altium Content Vault") (part "RES-2"))
    )
    (comp (ref "Signal1")
      (value "151031SS04000")
      (footprint "WL-TMRC_D3.95H5.3")
      (description "Led, Red, T-1 (3Mm), 635 Nm, 2 V, 30 Ma, 160 Mcd")
      (libsource (lib "Altium Content Vault") (part "LED_Red_1A-2K"))
    )
    (comp (ref "Signal2")
      (value "151031SS04000")
      (footprint "WL-TMRC_D3.95H5.3")
      (description "Led, Red, T-1 (3Mm), 635 Nm, 2 V, 30 Ma, 160 Mcd")
      (libsource (lib "Altium Content Vault") (part "LED_Red_1A-2K"))
    )
    (comp (ref "Signal3")
      (value "151031SS04000")
      (footprint "WL-TMRC_D3.95H5.3")
      (description "Led, Red, T-1 (3Mm), 635 Nm, 2 V, 30 Ma, 160 Mcd")
      (libsource (lib "Altium Content Vault") (part "LED_Red_1A-2K"))
    )
    (comp (ref "Signal4")
      (value "151031SS04000")
      (footprint "WL-TMRC_D3.95H5.3")
      (description "Led, Red, T-1 (3Mm), 635 Nm, 2 V, 30 Ma, 160 Mcd")
      (libsource (lib "Altium Content Vault") (part "LED_Red_1A-2K"))
    )
    (comp (ref "Signal5")
      (value "151031SS04000")
      (footprint "WL-TMRC_D3.95H5.3")
      (description "Led, Red, T-1 (3Mm), 635 Nm, 2 V, 30 Ma, 160 Mcd")
      (libsource (lib "Altium Content Vault") (part "LED_Red_1A-2K"))
    )
    (comp (ref "Signal6")
      (value "151031SS04000")
      (footprint "WL-TMRC_D3.95H5.3")
      (description "Led, Red, T-1 (3Mm), 635 Nm, 2 V, 30 Ma, 160 Mcd")
      (libsource (lib "Altium Content Vault") (part "LED_Red_1A-2K"))
    )
    (comp (ref "UBT")
      (value "61300211121")
      (footprint "61300211121")
      (libsource (lib "Altium Content Vault") (part "Header_Male_1R_02P"))
    )
    (comp (ref "UGT")
      (value "61300211121")
      (footprint "61300211121")
      (libsource (lib "Altium Content Vault") (part "Header_Male_1R_02P"))
    )
    (comp (ref "VBT")
      (value "61300211121")
      (footprint "61300211121")
      (libsource (lib "Altium Content Vault") (part "Header_Male_1R_02P"))
    )
    (comp (ref "VGT")
      (value "61300211121")
      (footprint "61300211121")
      (libsource (lib "Altium Content Vault") (part "Header_Male_1R_02P"))
    )
    (comp (ref "WBT")
      (value "61300211121")
      (footprint "61300211121")
      (libsource (lib "Altium Content Vault") (part "Header_Male_1R_02P"))
    )
    (comp (ref "WGT")
      (value "61300211121")
      (footprint "61300211121")
      (libsource (lib "Altium Content Vault") (part "Header_Male_1R_02P"))
    )
    (comp (ref "ZD1")
      (value "1N4749A")
      (footprint "FAIR-DO-41-2_V")
      (description "Zener Diode, 4.7V, 500mW, 5%, -65 to 200 degC, 2-Pin DO-41, Body 2.72 x 5.2 mm, RoHS")
      (fields (field (name "MANUFACTURER") "Fairchild Semiconductor") (field (name "TOLERANCE") "5%"))
      (libsource (lib "Altium Content Vault") (part "FAIR-DZEN-A1K2-2"))
    )
    (comp (ref "ZD2")
      (value "1N4749A")
      (footprint "FAIR-DO-41-2_V")
      (description "Zener Diode, 15V, 500mW, 5%, -65 to 200 degC, 2-Pin DO-41, Body 2.72 x 5.2 mm, RoHS")
      (fields (field (name "MANUFACTURER") "Fairchild Semiconductor") (field (name "TOLERANCE") "5%"))
      (libsource (lib "Altium Content Vault") (part "FAIR-DZEN-A1K2-2"))
    )
    (comp (ref "ZD3")
      (value "1N4749A")
      (footprint "FAIR-DO-41-2_V")
      (description "Zener Diode, 15V, 500mW, 5%, -65 to 200 degC, 2-Pin DO-41, Body 2.72 x 5.2 mm, RoHS")
      (fields (field (name "MANUFACTURER") "Fairchild Semiconductor") (field (name "TOLERANCE") "5%"))
      (libsource (lib "Altium Content Vault") (part "FAIR-DZEN-A1K2-2"))
    )
    (comp (ref "ZD4")
      (value "1N4749A")
      (footprint "FAIR-DO-41-2_V")
      (description "Zener Diode, 4.7V, 500mW, 5%, -65 to 200 degC, 2-Pin DO-41, Body 2.72 x 5.2 mm, RoHS")
      (fields (field (name "MANUFACTURER") "Fairchild Semiconductor") (field (name "TOLERANCE") "5%"))
      (libsource (lib "Altium Content Vault") (part "FAIR-DZEN-A1K2-2"))
    )
    (comp (ref "ZD5")
      (value "1N4749A")
      (footprint "FAIR-DO-41-2_V")
      (description "Zener Diode, 15V, 500mW, 5%, -65 to 200 degC, 2-Pin DO-41, Body 2.72 x 5.2 mm, RoHS")
      (fields (field (name "MANUFACTURER") "Fairchild Semiconductor") (field (name "TOLERANCE") "5%"))
      (libsource (lib "Altium Content Vault") (part "FAIR-DZEN-A1K2-2"))
    )
    (comp (ref "ZD6")
      (value "6")
      (footprint "FAIR-DO-41-2_V")
      (description "Zener Diode, 15V, 500mW, 5%, -65 to 200 degC, 2-Pin DO-41, Body 2.72 x 5.2 mm, RoHS")
      (fields (field (name "MANUFACTURER") "Fairchild Semiconductor") (field (name "TOLERANCE") "5%"))
      (libsource (lib "Altium Content Vault") (part "FAIR-DZEN-A1K2-2"))
    )
    (comp (ref "ZD7")
      (value "1N4749A")
      (footprint "FAIR-DO-41-2_V")
      (description "Zener Diode, 4.7V, 500mW, 5%, -65 to 200 degC, 2-Pin DO-41, Body 2.72 x 5.2 mm, RoHS")
      (fields (field (name "MANUFACTURER") "Fairchild Semiconductor") (field (name "TOLERANCE") "5%"))
      (libsource (lib "Altium Content Vault") (part "FAIR-DZEN-A1K2-2"))
    )
    (comp (ref "ZD8")
      (value "1N4749A")
      (footprint "FAIR-DO-41-2_V")
      (description "Zener Diode, 15V, 500mW, 5%, -65 to 200 degC, 2-Pin DO-41, Body 2.72 x 5.2 mm, RoHS")
      (fields (field (name "MANUFACTURER") "Fairchild Semiconductor") (field (name "TOLERANCE") "5%"))
      (libsource (lib "Altium Content Vault") (part "FAIR-DZEN-A1K2-2"))
    )
    (comp (ref "ZD9")
      (value "1N4749A")
      (footprint "FAIR-DO-41-2_V")
      (description "Zener Diode, 15V, 500mW, 5%, -65 to 200 degC, 2-Pin DO-41, Body 2.72 x 5.2 mm, RoHS")
      (fields (field (name "MANUFACTURER") "Fairchild Semiconductor") (field (name "TOLERANCE") "5%"))
      (libsource (lib "Altium Content Vault") (part "FAIR-DZEN-A1K2-2"))
    )
    (comp (ref "ZD10")
      (value "1N4749A")
      (footprint "FAIR-DO-41-2_V")
      (description "Zener Diode, 4.7V, 500mW, 5%, -65 to 200 degC, 2-Pin DO-41, Body 2.72 x 5.2 mm, RoHS")
      (fields (field (name "MANUFACTURER") "Fairchild Semiconductor") (field (name "TOLERANCE") "5%"))
      (libsource (lib "Altium Content Vault") (part "FAIR-DZEN-A1K2-2"))
    )
    (comp (ref "ZD11")
      (value "1N4749A")
      (footprint "FAIR-DO-41-2_V")
      (description "Zener Diode, 15V, 500mW, 5%, -65 to 200 degC, 2-Pin DO-41, Body 2.72 x 5.2 mm, RoHS")
      (fields (field (name "MANUFACTURER") "Fairchild Semiconductor") (field (name "TOLERANCE") "5%"))
      (libsource (lib "Altium Content Vault") (part "FAIR-DZEN-A1K2-2"))
    )
    (comp (ref "ZD12")
      (value "1N4749A")
      (footprint "FAIR-DO-41-2_V")
      (description "Zener Diode, 15V, 500mW, 5%, -65 to 200 degC, 2-Pin DO-41, Body 2.72 x 5.2 mm, RoHS")
      (fields (field (name "MANUFACTURER") "Fairchild Semiconductor") (field (name "TOLERANCE") "5%"))
      (libsource (lib "Altium Content Vault") (part "FAIR-DZEN-A1K2-2"))
    )
    (comp (ref "ZD13")
      (value "1N4749A")
      (footprint "FAIR-DO-41-2_V")
      (description "Zener Diode, 4.7V, 500mW, 5%, -65 to 200 degC, 2-Pin DO-41, Body 2.72 x 5.2 mm, RoHS")
      (fields (field (name "MANUFACTURER") "Fairchild Semiconductor") (field (name "TOLERANCE") "5%"))
      (libsource (lib "Altium Content Vault") (part "FAIR-DZEN-A1K2-2"))
    )
    (comp (ref "ZD14")
      (value "1N4749A")
      (footprint "FAIR-DO-41-2_V")
      (description "Zener Diode, 15V, 500mW, 5%, -65 to 200 degC, 2-Pin DO-41, Body 2.72 x 5.2 mm, RoHS")
      (fields (field (name "MANUFACTURER") "Fairchild Semiconductor") (field (name "TOLERANCE") "5%"))
      (libsource (lib "Altium Content Vault") (part "FAIR-DZEN-A1K2-2"))
    )
    (comp (ref "ZD15")
      (value "1N4749A")
      (footprint "FAIR-DO-41-2_V")
      (description "Zener Diode, 15V, 500mW, 5%, -65 to 200 degC, 2-Pin DO-41, Body 2.72 x 5.2 mm, RoHS")
      (fields (field (name "MANUFACTURER") "Fairchild Semiconductor") (field (name "TOLERANCE") "5%"))
      (libsource (lib "Altium Content Vault") (part "FAIR-DZEN-A1K2-2"))
    )
    (comp (ref "ZD16")
      (value "1N4749A")
      (footprint "FAIR-DO-41-2_V")
      (description "Zener Diode, 4.7V, 500mW, 5%, -65 to 200 degC, 2-Pin DO-41, Body 2.72 x 5.2 mm, RoHS")
      (fields (field (name "MANUFACTURER") "Fairchild Semiconductor") (field (name "TOLERANCE") "5%"))
      (libsource (lib "Altium Content Vault") (part "FAIR-DZEN-A1K2-2"))
    )
    (comp (ref "ZD17")
      (value "1N4749A")
      (footprint "FAIR-DO-41-2_V")
      (description "Zener Diode, 15V, 500mW, 5%, -65 to 200 degC, 2-Pin DO-41, Body 2.72 x 5.2 mm, RoHS")
      (fields (field (name "MANUFACTURER") "Fairchild Semiconductor") (field (name "TOLERANCE") "5%"))
      (libsource (lib "Altium Content Vault") (part "FAIR-DZEN-A1K2-2"))
    )
    (comp (ref "ZD18")
      (value "1N4749A")
      (footprint "FAIR-DO-41-2_V")
      (description "Zener Diode, 15V, 500mW, 5%, -65 to 200 degC, 2-Pin DO-41, Body 2.72 x 5.2 mm, RoHS")
      (fields (field (name "MANUFACTURER") "Fairchild Semiconductor") (field (name "TOLERANCE") "5%"))
      (libsource (lib "Altium Content Vault") (part "FAIR-DZEN-A1K2-2"))
    )
  )
  (nets
    (net (code "1") (name "/VGE_UN") (class "Default")
      (node (ref "D4") (pin "1") (pinfunction "A_1") (pintype "passive"))
      (node (ref "R23") (pin "2") (pinfunction "2_2") (pintype "passive"))
      (node (ref "R24") (pin "1") (pinfunction "1_1") (pintype "passive"))
      (node (ref "UBT") (pin "1") (pinfunction "1_1") (pintype "passive"))
      (node (ref "ZD11") (pin "1") (pinfunction "A_1") (pintype "passive"))
    )
    (net (code "2") (name "/VGE_UP") (class "Default")
      (node (ref "D1") (pin "1") (pinfunction "A_1") (pintype "passive"))
      (node (ref "R5") (pin "2") (pinfunction "2_2") (pintype "passive"))
      (node (ref "R6") (pin "1") (pinfunction "1_1") (pintype "passive"))
      (node (ref "UGT") (pin "1") (pinfunction "1_1") (pintype "passive"))
      (node (ref "ZD2") (pin "1") (pinfunction "A_1") (pintype "passive"))
    )
    (net (code "3") (name "/VGE_VN") (class "Default")
      (node (ref "D5") (pin "1") (pinfunction "A_1") (pintype "passive"))
      (node (ref "R29") (pin "2") (pinfunction "2_2") (pintype "passive"))
      (node (ref "R30") (pin "1") (pinfunction "1_1") (pintype "passive"))
      (node (ref "VBT") (pin "1") (pinfunction "1_1") (pintype "passive"))
      (node (ref "ZD14") (pin "1") (pinfunction "A_1") (pintype "passive"))
    )
    (net (code "4") (name "/VGE_VP") (class "Default")
      (node (ref "D2") (pin "1") (pinfunction "A_1") (pintype "passive"))
      (node (ref "R11") (pin "2") (pinfunction "2_2") (pintype "passive"))
      (node (ref "R12") (pin "1") (pinfunction "1_1") (pintype "passive"))
      (node (ref "VGT") (pin "1") (pinfunction "1_1") (pintype "passive"))
      (node (ref "ZD5") (pin "1") (pinfunction "A_1") (pintype "passive"))
    )
    (net (code "5") (name "/VGE_WN") (class "Default")
      (node (ref "D6") (pin "1") (pinfunction "A_1") (pintype "passive"))
      (node (ref "R35") (pin "2") (pinfunction "2_2") (pintype "passive"))
      (node (ref "R36") (pin "1") (pinfunction "1_1") (pintype "passive"))
      (node (ref "WBT") (pin "1") (pinfunction "1_1") (pintype "passive"))
      (node (ref "ZD17") (pin "1") (pinfunction "A_1") (pintype "passive"))
    )
    (net (code "6") (name "/VGE_WP") (class "Default")
      (node (ref "D3") (pin "1") (pinfunction "A_1") (pintype "passive"))
      (node (ref "R17") (pin "2") (pinfunction "2_2") (pintype "passive"))
      (node (ref "R18") (pin "1") (pinfunction "1_1") (pintype "passive"))
      (node (ref "WGT") (pin "1") (pinfunction "1_1") (pintype "passive"))
      (node (ref "ZD8") (pin "1") (pinfunction "A_1") (pintype "passive"))
    )
    (net (code "7") (name "/ePWM1A") (class "Default")
      (node (ref "R1") (pin "1") (pinfunction "1_1") (pintype "passive"))
      (node (ref "R2") (pin "1") (pinfunction "1_1") (pintype "passive"))
      (node (ref "ePWM") (pin "1") (pinfunction "1_1") (pintype "passive"))
    )
    (net (code "8") (name "/ePWM1B") (class "Default")
      (node (ref "R19") (pin "1") (pinfunction "1_1") (pintype "passive"))
      (node (ref "R20") (pin "1") (pinfunction "1_1") (pintype "passive"))
      (node (ref "ePWM") (pin "4") (pinfunction "4_4") (pintype "passive"))
    )
    (net (code "9") (name "/ePWM2A") (class "Default")
      (node (ref "R7") (pin "1") (pinfunction "1_1") (pintype "passive"))
      (node (ref "R8") (pin "1") (pinfunction "1_1") (pintype "passive"))
      (node (ref "ePWM") (pin "2") (pinfunction "2_2") (pintype "passive"))
    )
    (net (code "10") (name "/ePWM2B") (class "Default")
      (node (ref "R25") (pin "1") (pinfunction "1_1") (pintype "passive"))
      (node (ref "R26") (pin "1") (pinfunction "1_1") (pintype "passive"))
      (node (ref "ePWM") (pin "5") (pinfunction "5_5") (pintype "passive"))
    )
    (net (code "11") (name "/ePWM3A") (class "Default")
      (node (ref "R13") (pin "1") (pinfunction "1_1") (pintype "passive"))
      (node (ref "R14") (pin "1") (pinfunction "1_1") (pintype "passive"))
      (node (ref "ePWM") (pin "3") (pinfunction "3_3") (pintype "passive"))
    )
    (net (code "12") (name "/ePWM3B") (class "Default")
      (node (ref "R31") (pin "1") (pinfunction "1_1") (pintype "passive"))
      (node (ref "R32") (pin "1") (pinfunction "1_1") (pintype "passive"))
      (node (ref "ePWM") (pin "6") (pinfunction "6_6") (pintype "passive"))
    )
    (net (code "13") (name "DSP_GND") (class "Default")
      (node (ref "IC1") (pin "1") (pinfunction "NC_1") (pintype "bidirectional"))
      (node (ref "IC1") (pin "3") (pinfunction "K_3") (pintype "bidirectional"))
      (node (ref "IC1") (pin "4") (pinfunction "NC_4") (pintype "bidirectional"))
      (node (ref "IC2") (pin "1") (pinfunction "NC_1") (pintype "bidirectional"))
      (node (ref "IC2") (pin "3") (pinfunction "K_3") (pintype "bidirectional"))
      (node (ref "IC2") (pin "4") (pinfunction "NC_4") (pintype "bidirectional"))
      (node (ref "IC3") (pin "1") (pinfunction "NC_1") (pintype "bidirectional"))
      (node (ref "IC3") (pin "3") (pinfunction "K_3") (pintype "bidirectional"))
      (node (ref "IC3") (pin "4") (pinfunction "NC_4") (pintype "bidirectional"))
      (node (ref "IC4") (pin "1") (pinfunction "NC_1") (pintype "bidirectional"))
      (node (ref "IC4") (pin "3") (pinfunction "K_3") (pintype "bidirectional"))
      (node (ref "IC4") (pin "4") (pinfunction "NC_4") (pintype "bidirectional"))
      (node (ref "IC5") (pin "1") (pinfunction "NC_1") (pintype "bidirectional"))
      (node (ref "IC5") (pin "3") (pinfunction "K_3") (pintype "bidirectional"))
      (node (ref "IC5") (pin "4") (pinfunction "NC_4") (pintype "bidirectional"))
      (node (ref "IC6") (pin "1") (pinfunction "NC_1") (pintype "bidirectional"))
      (node (ref "IC6") (pin "3") (pinfunction "K_3") (pintype "bidirectional"))
      (node (ref "IC6") (pin "4") (pinfunction "NC_4") (pintype "bidirectional"))
      (node (ref "Signal1") (pin "2") (pinfunction "K_2") (pintype "passive"))
      (node (ref "Signal2") (pin "2") (pinfunction "K_2") (pintype "passive"))
      (node (ref "Signal3") (pin "2") (pinfunction "K_2") (pintype "passive"))
      (node (ref "Signal4") (pin "2") (pinfunction "K_2") (pintype "passive"))
      (node (ref "Signal5") (pin "2") (pinfunction "K_2") (pintype "passive"))
      (node (ref "Signal6") (pin "2") (pinfunction "K_2") (pintype "passive"))
      (node (ref "ePWM") (pin "7") (pinfunction "7_7") (pintype "passive"))
    )
    (net (code "14") (name "D_C") (class "Default")
      (node (ref "C17") (pin "2") (pinfunction "2_2") (pintype "passive"))
      (node (ref "C18") (pin "2") (pinfunction "2_2") (pintype "passive"))
      (node (ref "C19") (pin "1") (pinfunction "C_1") (pintype "passive"))
      (node (ref "C20") (pin "2") (pinfunction "A_2") (pintype "passive"))
      (node (ref "C22") (pin "2") (pinfunction "2_2") (pintype "passive"))
      (node (ref "C23") (pin "2") (pinfunction "2_2") (pintype "passive"))
      (node (ref "C24") (pin "1") (pinfunction "C_1") (pintype "passive"))
      (node (ref "C25") (pin "2") (pinfunction "A_2") (pintype "passive"))
      (node (ref "C27") (pin "2") (pinfunction "2_2") (pintype "passive"))
      (node (ref "C28") (pin "2") (pinfunction "2_2") (pintype "passive"))
      (node (ref "C29") (pin "1") (pinfunction "C_1") (pintype "passive"))
      (node (ref "C30") (pin "2") (pinfunction "A_2") (pintype "passive"))
      (node (ref "JBT") (pin "2") (pinfunction "2_2") (pintype "passive"))
      (node (ref "Power4") (pin "2") (pinfunction "K_2") (pintype "passive"))
      (node (ref "Power5") (pin "2") (pinfunction "K_2") (pintype "passive"))
      (node (ref "Power6") (pin "2") (pinfunction "K_2") (pintype "passive"))
      (node (ref "R21") (pin "2") (pinfunction "2_2") (pintype "passive"))
      (node (ref "R24") (pin "2") (pinfunction "2_2") (pintype "passive"))
      (node (ref "R27") (pin "2") (pinfunction "2_2") (pintype "passive"))
      (node (ref "R30") (pin "2") (pinfunction "2_2") (pintype "passive"))
      (node (ref "R33") (pin "2") (pinfunction "2_2") (pintype "passive"))
      (node (ref "R36") (pin "2") (pinfunction "2_2") (pintype "passive"))
      (node (ref "UBT") (pin "2") (pinfunction "2_2") (pintype "passive"))
      (node (ref "VBT") (pin "2") (pinfunction "2_2") (pintype "passive"))
      (node (ref "WBT") (pin "2") (pinfunction "2_2") (pintype "passive"))
      (node (ref "ZD10") (pin "2") (pinfunction "K_2") (pintype "passive"))
      (node (ref "ZD12") (pin "1") (pinfunction "A_1") (pintype "passive"))
      (node (ref "ZD13") (pin "2") (pinfunction "K_2") (pintype "passive"))
      (node (ref "ZD15") (pin "1") (pinfunction "A_1") (pintype "passive"))
      (node (ref "ZD16") (pin "2") (pinfunction "K_2") (pintype "passive"))
      (node (ref "ZD18") (pin "1") (pinfunction "A_1") (pintype "passive"))
    )
    (net (code "15") (name "Net-(D1-K)") (class "Default")
      (node (ref "D1") (pin "2") (pinfunction "K_2") (pintype "passive"))
      (node (ref "IC1") (pin "6") (pinfunction "VO_6") (pintype "bidirectional"))
      (node (ref "IC1") (pin "7") (pinfunction "VO_7") (pintype "bidirectional"))
      (node (ref "R5") (pin "1") (pinfunction "1_1") (pintype "passive"))
    )
    (net (code "16") (name "Net-(D2-K)") (class "Default")
      (node (ref "D2") (pin "2") (pinfunction "K_2") (pintype "passive"))
      (node (ref "IC2") (pin "6") (pinfunction "VO_6") (pintype "bidirectional"))
      (node (ref "IC2") (pin "7") (pinfunction "VO_7") (pintype "bidirectional"))
      (node (ref "R11") (pin "1") (pinfunction "1_1") (pintype "passive"))
    )
    (net (code "17") (name "Net-(D3-K)") (class "Default")
      (node (ref "D3") (pin "2") (pinfunction "K_2") (pintype "passive"))
      (node (ref "IC3") (pin "6") (pinfunction "VO_6") (pintype "bidirectional"))
      (node (ref "IC3") (pin "7") (pinfunction "VO_7") (pintype "bidirectional"))
      (node (ref "R17") (pin "1") (pinfunction "1_1") (pintype "passive"))
    )
    (net (code "18") (name "Net-(D4-K)") (class "Default")
      (node (ref "D4") (pin "2") (pinfunction "K_2") (pintype "passive"))
      (node (ref "IC4") (pin "6") (pinfunction "VO_6") (pintype "bidirectional"))
      (node (ref "IC4") (pin "7") (pinfunction "VO_7") (pintype "bidirectional"))
      (node (ref "R23") (pin "1") (pinfunction "1_1") (pintype "passive"))
    )
    (net (code "19") (name "Net-(D5-K)") (class "Default")
      (node (ref "D5") (pin "2") (pinfunction "K_2") (pintype "passive"))
      (node (ref "IC5") (pin "6") (pinfunction "VO_6") (pintype "bidirectional"))
      (node (ref "IC5") (pin "7") (pinfunction "VO_7") (pintype "bidirectional"))
      (node (ref "R29") (pin "1") (pinfunction "1_1") (pintype "passive"))
    )
    (net (code "20") (name "Net-(D6-K)") (class "Default")
      (node (ref "D6") (pin "2") (pinfunction "K_2") (pintype "passive"))
      (node (ref "IC6") (pin "6") (pinfunction "VO_6") (pintype "bidirectional"))
      (node (ref "IC6") (pin "7") (pinfunction "VO_7") (pintype "bidirectional"))
      (node (ref "R35") (pin "1") (pinfunction "1_1") (pintype "passive"))
    )
    (net (code "21") (name "Net-(IC1-A)") (class "Default")
      (node (ref "IC1") (pin "2") (pinfunction "A_2") (pintype "bidirectional"))
      (node (ref "R2") (pin "2") (pinfunction "2_2") (pintype "passive"))
    )
    (net (code "22") (name "Net-(IC2-A)") (class "Default")
      (node (ref "IC2") (pin "2") (pinfunction "A_2") (pintype "bidirectional"))
      (node (ref "R8") (pin "2") (pinfunction "2_2") (pintype "passive"))
    )
    (net (code "23") (name "Net-(IC3-A)") (class "Default")
      (node (ref "IC3") (pin "2") (pinfunction "A_2") (pintype "bidirectional"))
      (node (ref "R14") (pin "2") (pinfunction "2_2") (pintype "passive"))
    )
    (net (code "24") (name "Net-(IC4-A)") (class "Default")
      (node (ref "IC4") (pin "2") (pinfunction "A_2") (pintype "bidirectional"))
      (node (ref "R20") (pin "2") (pinfunction "2_2") (pintype "passive"))
    )
    (net (code "25") (name "Net-(IC5-A)") (class "Default")
      (node (ref "IC5") (pin "2") (pinfunction "A_2") (pintype "bidirectional"))
      (node (ref "R26") (pin "2") (pinfunction "2_2") (pintype "passive"))
    )
    (net (code "26") (name "Net-(IC6-A)") (class "Default")
      (node (ref "IC6") (pin "2") (pinfunction "A_2") (pintype "bidirectional"))
      (node (ref "R32") (pin "2") (pinfunction "2_2") (pintype "passive"))
    )
    (net (code "27") (name "Net-(Power1-A)") (class "Default")
      (node (ref "Power1") (pin "1") (pinfunction "A_1") (pintype "passive"))
      (node (ref "R4") (pin "2") (pinfunction "2_2") (pintype "passive"))
    )
    (net (code "28") (name "Net-(Power2-A)") (class "Default")
      (node (ref "Power2") (pin "1") (pinfunction "A_1") (pintype "passive"))
      (node (ref "R10") (pin "2") (pinfunction "2_2") (pintype "passive"))
    )
    (net (code "29") (name "Net-(Power3-A)") (class "Default")
      (node (ref "Power3") (pin "1") (pinfunction "A_1") (pintype "passive"))
      (node (ref "R16") (pin "2") (pinfunction "2_2") (pintype "passive"))
    )
    (net (code "30") (name "Net-(Power4-A)") (class "Default")
      (node (ref "Power4") (pin "1") (pinfunction "A_1") (pintype "passive"))
      (node (ref "R22") (pin "2") (pinfunction "2_2") (pintype "passive"))
    )
    (net (code "31") (name "Net-(Power5-A)") (class "Default")
      (node (ref "Power5") (pin "1") (pinfunction "A_1") (pintype "passive"))
      (node (ref "R28") (pin "2") (pinfunction "2_2") (pintype "passive"))
    )
    (net (code "32") (name "Net-(Power6-A)") (class "Default")
      (node (ref "Power6") (pin "1") (pinfunction "A_1") (pintype "passive"))
      (node (ref "R34") (pin "2") (pinfunction "2_2") (pintype "passive"))
    )
    (net (code "33") (name "Net-(Signal1-A)") (class "Default")
      (node (ref "R1") (pin "2") (pinfunction "2_2") (pintype "passive"))
      (node (ref "Signal1") (pin "1") (pinfunction "A_1") (pintype "passive"))
    )
    (net (code "34") (name "Net-(Signal2-A)") (class "Default")
      (node (ref "R7") (pin "2") (pinfunction "2_2") (pintype "passive"))
      (node (ref "Signal2") (pin "1") (pinfunction "A_1") (pintype "passive"))
    )
    (net (code "35") (name "Net-(Signal3-A)") (class "Default")
      (node (ref "R13") (pin "2") (pinfunction "2_2") (pintype "passive"))
      (node (ref "Signal3") (pin "1") (pinfunction "A_1") (pintype "passive"))
    )
    (net (code "36") (name "Net-(Signal4-A)") (class "Default")
      (node (ref "R19") (pin "2") (pinfunction "2_2") (pintype "passive"))
      (node (ref "Signal4") (pin "1") (pinfunction "A_1") (pintype "passive"))
    )
    (net (code "37") (name "Net-(Signal5-A)") (class "Default")
      (node (ref "R25") (pin "2") (pinfunction "2_2") (pintype "passive"))
      (node (ref "Signal5") (pin "1") (pinfunction "A_1") (pintype "passive"))
    )
    (net (code "38") (name "Net-(Signal6-A)") (class "Default")
      (node (ref "R31") (pin "2") (pinfunction "2_2") (pintype "passive"))
      (node (ref "Signal6") (pin "1") (pinfunction "A_1") (pintype "passive"))
    )
    (net (code "39") (name "Net-(ZD2-K)") (class "Default")
      (node (ref "ZD2") (pin "2") (pinfunction "K_2") (pintype "passive"))
      (node (ref "ZD3") (pin "2") (pinfunction "K_2") (pintype "passive"))
    )
    (net (code "40") (name "Net-(ZD5-K)") (class "Default")
      (node (ref "ZD5") (pin "2") (pinfunction "K_2") (pintype "passive"))
      (node (ref "ZD6") (pin "2") (pinfunction "K_2") (pintype "passive"))
    )
    (net (code "41") (name "Net-(ZD8-K)") (class "Default")
      (node (ref "ZD8") (pin "2") (pinfunction "K_2") (pintype "passive"))
      (node (ref "ZD9") (pin "2") (pinfunction "K_2") (pintype "passive"))
    )
    (net (code "42") (name "Net-(ZD11-K)") (class "Default")
      (node (ref "ZD11") (pin "2") (pinfunction "K_2") (pintype "passive"))
      (node (ref "ZD12") (pin "2") (pinfunction "K_2") (pintype "passive"))
    )
    (net (code "43") (name "Net-(ZD14-K)") (class "Default")
      (node (ref "ZD14") (pin "2") (pinfunction "K_2") (pintype "passive"))
      (node (ref "ZD15") (pin "2") (pinfunction "K_2") (pintype "passive"))
    )
    (net (code "44") (name "Net-(ZD17-K)") (class "Default")
      (node (ref "ZD17") (pin "2") (pinfunction "K_2") (pintype "passive"))
      (node (ref "ZD18") (pin "2") (pinfunction "K_2") (pintype "passive"))
    )
    (net (code "45") (name "U_G") (class "Default")
      (node (ref "C2") (pin "2") (pinfunction "2_2") (pintype "passive"))
      (node (ref "C3") (pin "2") (pinfunction "2_2") (pintype "passive"))
      (node (ref "C4") (pin "1") (pinfunction "C_1") (pintype "passive"))
      (node (ref "C5") (pin "2") (pinfunction "A_2") (pintype "passive"))
      (node (ref "JUT") (pin "2") (pinfunction "2_2") (pintype "passive"))
      (node (ref "Power1") (pin "2") (pinfunction "K_2") (pintype "passive"))
      (node (ref "R3") (pin "2") (pinfunction "2_2") (pintype "passive"))
      (node (ref "R6") (pin "2") (pinfunction "2_2") (pintype "passive"))
      (node (ref "UGT") (pin "2") (pinfunction "2_2") (pintype "passive"))
      (node (ref "ZD1") (pin "2") (pinfunction "K_2") (pintype "passive"))
      (node (ref "ZD3") (pin "1") (pinfunction "A_1") (pintype "passive"))
    )
    (net (code "46") (name "VCC_B") (class "Default")
      (node (ref "C16") (pin "1") (pinfunction "1_1") (pintype "passive"))
      (node (ref "C17") (pin "1") (pinfunction "1_1") (pintype "passive"))
      (node (ref "C19") (pin "2") (pinfunction "A_2") (pintype "passive"))
      (node (ref "C21") (pin "1") (pinfunction "1_1") (pintype "passive"))
      (node (ref "C22") (pin "1") (pinfunction "1_1") (pintype "passive"))
      (node (ref "C24") (pin "2") (pinfunction "A_2") (pintype "passive"))
      (node (ref "C26") (pin "1") (pinfunction "1_1") (pintype "passive"))
      (node (ref "C27") (pin "1") (pinfunction "1_1") (pintype "passive"))
      (node (ref "C29") (pin "2") (pinfunction "A_2") (pintype "passive"))
      (node (ref "IC4") (pin "8") (pinfunction "VCC_8") (pintype "bidirectional"))
      (node (ref "IC5") (pin "8") (pinfunction "VCC_8") (pintype "bidirectional"))
      (node (ref "IC6") (pin "8") (pinfunction "VCC_8") (pintype "bidirectional"))
      (node (ref "JBT") (pin "1") (pinfunction "1_1") (pintype "passive"))
      (node (ref "R21") (pin "1") (pinfunction "1_1") (pintype "passive"))
      (node (ref "R22") (pin "1") (pinfunction "1_1") (pintype "passive"))
      (node (ref "R27") (pin "1") (pinfunction "1_1") (pintype "passive"))
      (node (ref "R28") (pin "1") (pinfunction "1_1") (pintype "passive"))
      (node (ref "R33") (pin "1") (pinfunction "1_1") (pintype "passive"))
      (node (ref "R34") (pin "1") (pinfunction "1_1") (pintype "passive"))
    )
    (net (code "47") (name "VCC_U_T") (class "Default")
      (node (ref "C1") (pin "1") (pinfunction "1_1") (pintype "passive"))
      (node (ref "C2") (pin "1") (pinfunction "1_1") (pintype "passive"))
      (node (ref "C4") (pin "2") (pinfunction "A_2") (pintype "passive"))
      (node (ref "IC1") (pin "8") (pinfunction "VCC_8") (pintype "bidirectional"))
      (node (ref "JUT") (pin "1") (pinfunction "1_1") (pintype "passive"))
      (node (ref "R3") (pin "1") (pinfunction "1_1") (pintype "passive"))
      (node (ref "R4") (pin "1") (pinfunction "1_1") (pintype "passive"))
    )
    (net (code "48") (name "VCC_V_T") (class "Default")
      (node (ref "C6") (pin "1") (pinfunction "1_1") (pintype "passive"))
      (node (ref "C7") (pin "1") (pinfunction "1_1") (pintype "passive"))
      (node (ref "C9") (pin "2") (pinfunction "A_2") (pintype "passive"))
      (node (ref "IC2") (pin "8") (pinfunction "VCC_8") (pintype "bidirectional"))
      (node (ref "JVT") (pin "1") (pinfunction "1_1") (pintype "passive"))
      (node (ref "R10") (pin "1") (pinfunction "1_1") (pintype "passive"))
      (node (ref "R9") (pin "1") (pinfunction "1_1") (pintype "passive"))
    )
    (net (code "49") (name "VCC_W_T") (class "Default")
      (node (ref "C11") (pin "1") (pinfunction "1_1") (pintype "passive"))
      (node (ref "C12") (pin "1") (pinfunction "1_1") (pintype "passive"))
      (node (ref "C14") (pin "2") (pinfunction "A_2") (pintype "passive"))
      (node (ref "IC3") (pin "8") (pinfunction "VCC_8") (pintype "bidirectional"))
      (node (ref "JWT") (pin "1") (pinfunction "1_1") (pintype "passive"))
      (node (ref "R15") (pin "1") (pinfunction "1_1") (pintype "passive"))
      (node (ref "R16") (pin "1") (pinfunction "1_1") (pintype "passive"))
    )
    (net (code "50") (name "VEE_B") (class "Default")
      (node (ref "C16") (pin "2") (pinfunction "2_2") (pintype "passive"))
      (node (ref "C18") (pin "1") (pinfunction "1_1") (pintype "passive"))
      (node (ref "C20") (pin "1") (pinfunction "C_1") (pintype "passive"))
      (node (ref "C21") (pin "2") (pinfunction "2_2") (pintype "passive"))
      (node (ref "C23") (pin "1") (pinfunction "1_1") (pintype "passive"))
      (node (ref "C25") (pin "1") (pinfunction "C_1") (pintype "passive"))
      (node (ref "C26") (pin "2") (pinfunction "2_2") (pintype "passive"))
      (node (ref "C28") (pin "1") (pinfunction "1_1") (pintype "passive"))
      (node (ref "C30") (pin "1") (pinfunction "C_1") (pintype "passive"))
      (node (ref "IC4") (pin "5") (pinfunction "VEE_5") (pintype "bidirectional"))
      (node (ref "IC5") (pin "5") (pinfunction "VEE_5") (pintype "bidirectional"))
      (node (ref "IC6") (pin "5") (pinfunction "VEE_5") (pintype "bidirectional"))
      (node (ref "JBT") (pin "3") (pinfunction "3_3") (pintype "passive"))
      (node (ref "ZD10") (pin "1") (pinfunction "A_1") (pintype "passive"))
      (node (ref "ZD13") (pin "1") (pinfunction "A_1") (pintype "passive"))
      (node (ref "ZD16") (pin "1") (pinfunction "A_1") (pintype "passive"))
    )
    (net (code "51") (name "VEE_U_T") (class "Default")
      (node (ref "C1") (pin "2") (pinfunction "2_2") (pintype "passive"))
      (node (ref "C3") (pin "1") (pinfunction "1_1") (pintype "passive"))
      (node (ref "C5") (pin "1") (pinfunction "C_1") (pintype "passive"))
      (node (ref "IC1") (pin "5") (pinfunction "VEE_5") (pintype "bidirectional"))
      (node (ref "JUT") (pin "3") (pinfunction "3_3") (pintype "passive"))
      (node (ref "ZD1") (pin "1") (pinfunction "A_1") (pintype "passive"))
    )
    (net (code "52") (name "VEE_V_T") (class "Default")
      (node (ref "C10") (pin "1") (pinfunction "C_1") (pintype "passive"))
      (node (ref "C6") (pin "2") (pinfunction "2_2") (pintype "passive"))
      (node (ref "C8") (pin "1") (pinfunction "1_1") (pintype "passive"))
      (node (ref "IC2") (pin "5") (pinfunction "VEE_5") (pintype "bidirectional"))
      (node (ref "JVT") (pin "3") (pinfunction "3_3") (pintype "passive"))
      (node (ref "ZD4") (pin "1") (pinfunction "A_1") (pintype "passive"))
    )
    (net (code "53") (name "VEE_W_T") (class "Default")
      (node (ref "C11") (pin "2") (pinfunction "2_2") (pintype "passive"))
      (node (ref "C13") (pin "1") (pinfunction "1_1") (pintype "passive"))
      (node (ref "C15") (pin "1") (pinfunction "C_1") (pintype "passive"))
      (node (ref "IC3") (pin "5") (pinfunction "VEE_5") (pintype "bidirectional"))
      (node (ref "JWT") (pin "3") (pinfunction "3_3") (pintype "passive"))
      (node (ref "ZD7") (pin "1") (pinfunction "A_1") (pintype "passive"))
    )
    (net (code "54") (name "V_G") (class "Default")
      (node (ref "C10") (pin "2") (pinfunction "A_2") (pintype "passive"))
      (node (ref "C7") (pin "2") (pinfunction "2_2") (pintype "passive"))
      (node (ref "C8") (pin "2") (pinfunction "2_2") (pintype "passive"))
      (node (ref "C9") (pin "1") (pinfunction "C_1") (pintype "passive"))
      (node (ref "JVT") (pin "2") (pinfunction "2_2") (pintype "passive"))
      (node (ref "Power2") (pin "2") (pinfunction "K_2") (pintype "passive"))
      (node (ref "R12") (pin "2") (pinfunction "2_2") (pintype "passive"))
      (node (ref "R9") (pin "2") (pinfunction "2_2") (pintype "passive"))
      (node (ref "VGT") (pin "2") (pinfunction "2_2") (pintype "passive"))
      (node (ref "ZD4") (pin "2") (pinfunction "K_2") (pintype "passive"))
      (node (ref "ZD6") (pin "1") (pinfunction "A_1") (pintype "passive"))
    )
    (net (code "55") (name "W_G") (class "Default")
      (node (ref "C12") (pin "2") (pinfunction "2_2") (pintype "passive"))
      (node (ref "C13") (pin "2") (pinfunction "2_2") (pintype "passive"))
      (node (ref "C14") (pin "1") (pinfunction "C_1") (pintype "passive"))
      (node (ref "C15") (pin "2") (pinfunction "A_2") (pintype "passive"))
      (node (ref "JWT") (pin "2") (pinfunction "2_2") (pintype "passive"))
      (node (ref "Power3") (pin "2") (pinfunction "K_2") (pintype "passive"))
      (node (ref "R15") (pin "2") (pinfunction "2_2") (pintype "passive"))
      (node (ref "R18") (pin "2") (pinfunction "2_2") (pintype "passive"))
      (node (ref "WGT") (pin "2") (pinfunction "2_2") (pintype "passive"))
      (node (ref "ZD7") (pin "2") (pinfunction "K_2") (pintype "passive"))
      (node (ref "ZD9") (pin "1") (pinfunction "A_1") (pintype "passive"))
    )
  )
)
